# Light_interrupter.net
KiCad netlist of a schematic drawn in Altium Designer
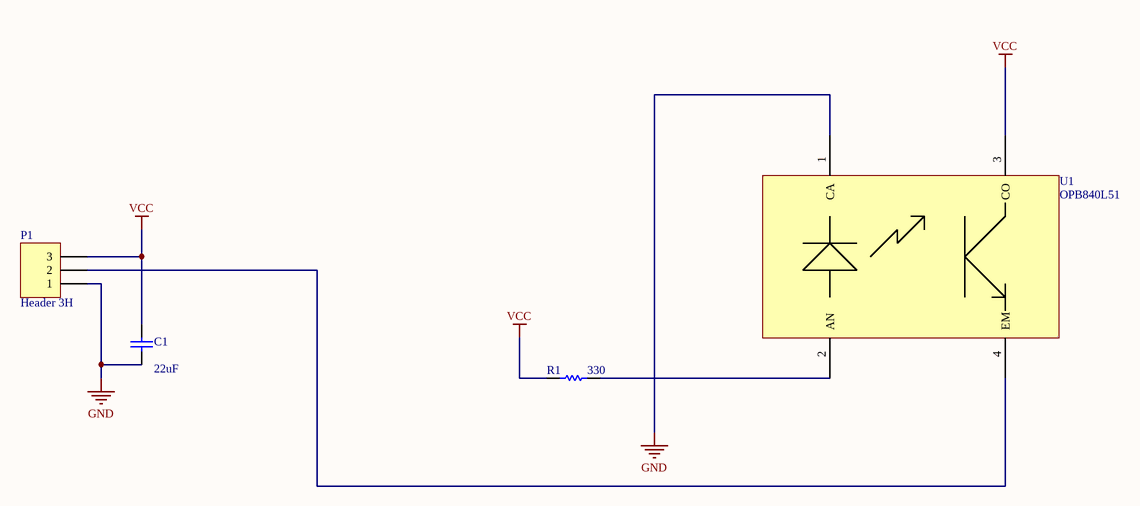
[diagram p0: Light interrupter.SchDoc]

(export (version "E")
  (design (tool "Eeschema 10.0.6"))
  (components
    (comp (ref "C1")
      (value "22uF")
      (footprint "1608[0603]")
      (description "Capacitor")
      (fields (field (name "PUBLISHER") "Altium Limited"))
      (libsource (lib "Miscellaneous Devices") (part "Cap"))
    )
    (comp (ref "P1")
      (value "Header 3H")
      (footprint "HDR1X3H")
      (description "Header, 3-Pin, Right Angle")
      (fields (field (name "PUBLISHER") "Altium Limited"))
      (libsource (lib "Miscellaneous Connectors") (part "Header 3H"))
    )
    (comp (ref "R1")
      (value "330")
      (footprint "1608[0603]")
      (description "Semiconductor Resistor")
      (fields (field (name "PUBLISHER") "Altium Limited"))
      (libsource (lib "Miscellaneous Devices") (part "Res Semi"))
    )
    (comp (ref "U1")
      (value "OPB840L51")
      (footprint "OPB840L51_Housing")
      (description "Slotted Optical Switch, TT electronics")
      (libsource (lib "OPB840L51") (part "OPB840L51"))
    )
  )
  (nets
    (net (code "1") (name "GND") (class "Default")
      (node (ref "C1") (pin "1") (pinfunction "1_1") (pintype "passive"))
      (node (ref "P1") (pin "1") (pinfunction "1_1") (pintype "passive"))
      (node (ref "U1") (pin "1") (pinfunction "CA_1") (pintype "passive"))
    )
    (net (code "2") (name "Net-(U1-AN)") (class "Default")
      (node (ref "R1") (pin "2") (pinfunction "2_2") (pintype "passive"))
      (node (ref "U1") (pin "2") (pinfunction "AN_2") (pintype "passive"))
    )
    (net (code "3") (name "Net-(U1-EM)") (class "Default")
      (node (ref "P1") (pin "2") (pinfunction "2_2") (pintype "passive"))
      (node (ref "U1") (pin "4") (pinfunction "EM_4") (pintype "passive"))
    )
    (net (code "4") (name "VCC") (class "Default")
      (node (ref "C1") (pin "2") (pinfunction "2_2") (pintype "passive"))
      (node (ref "P1") (pin "3") (pinfunction "3_3") (pintype "passive"))
      (node (ref "R1") (pin "1") (pinfunction "1_1") (pintype "passive"))
      (node (ref "U1") (pin "3") (pinfunction "CO_3") (pintype "passive"))
    )
  )
)
